# ESP32-C3.net
KiCad netlist of a schematic drawn in Altium Designer
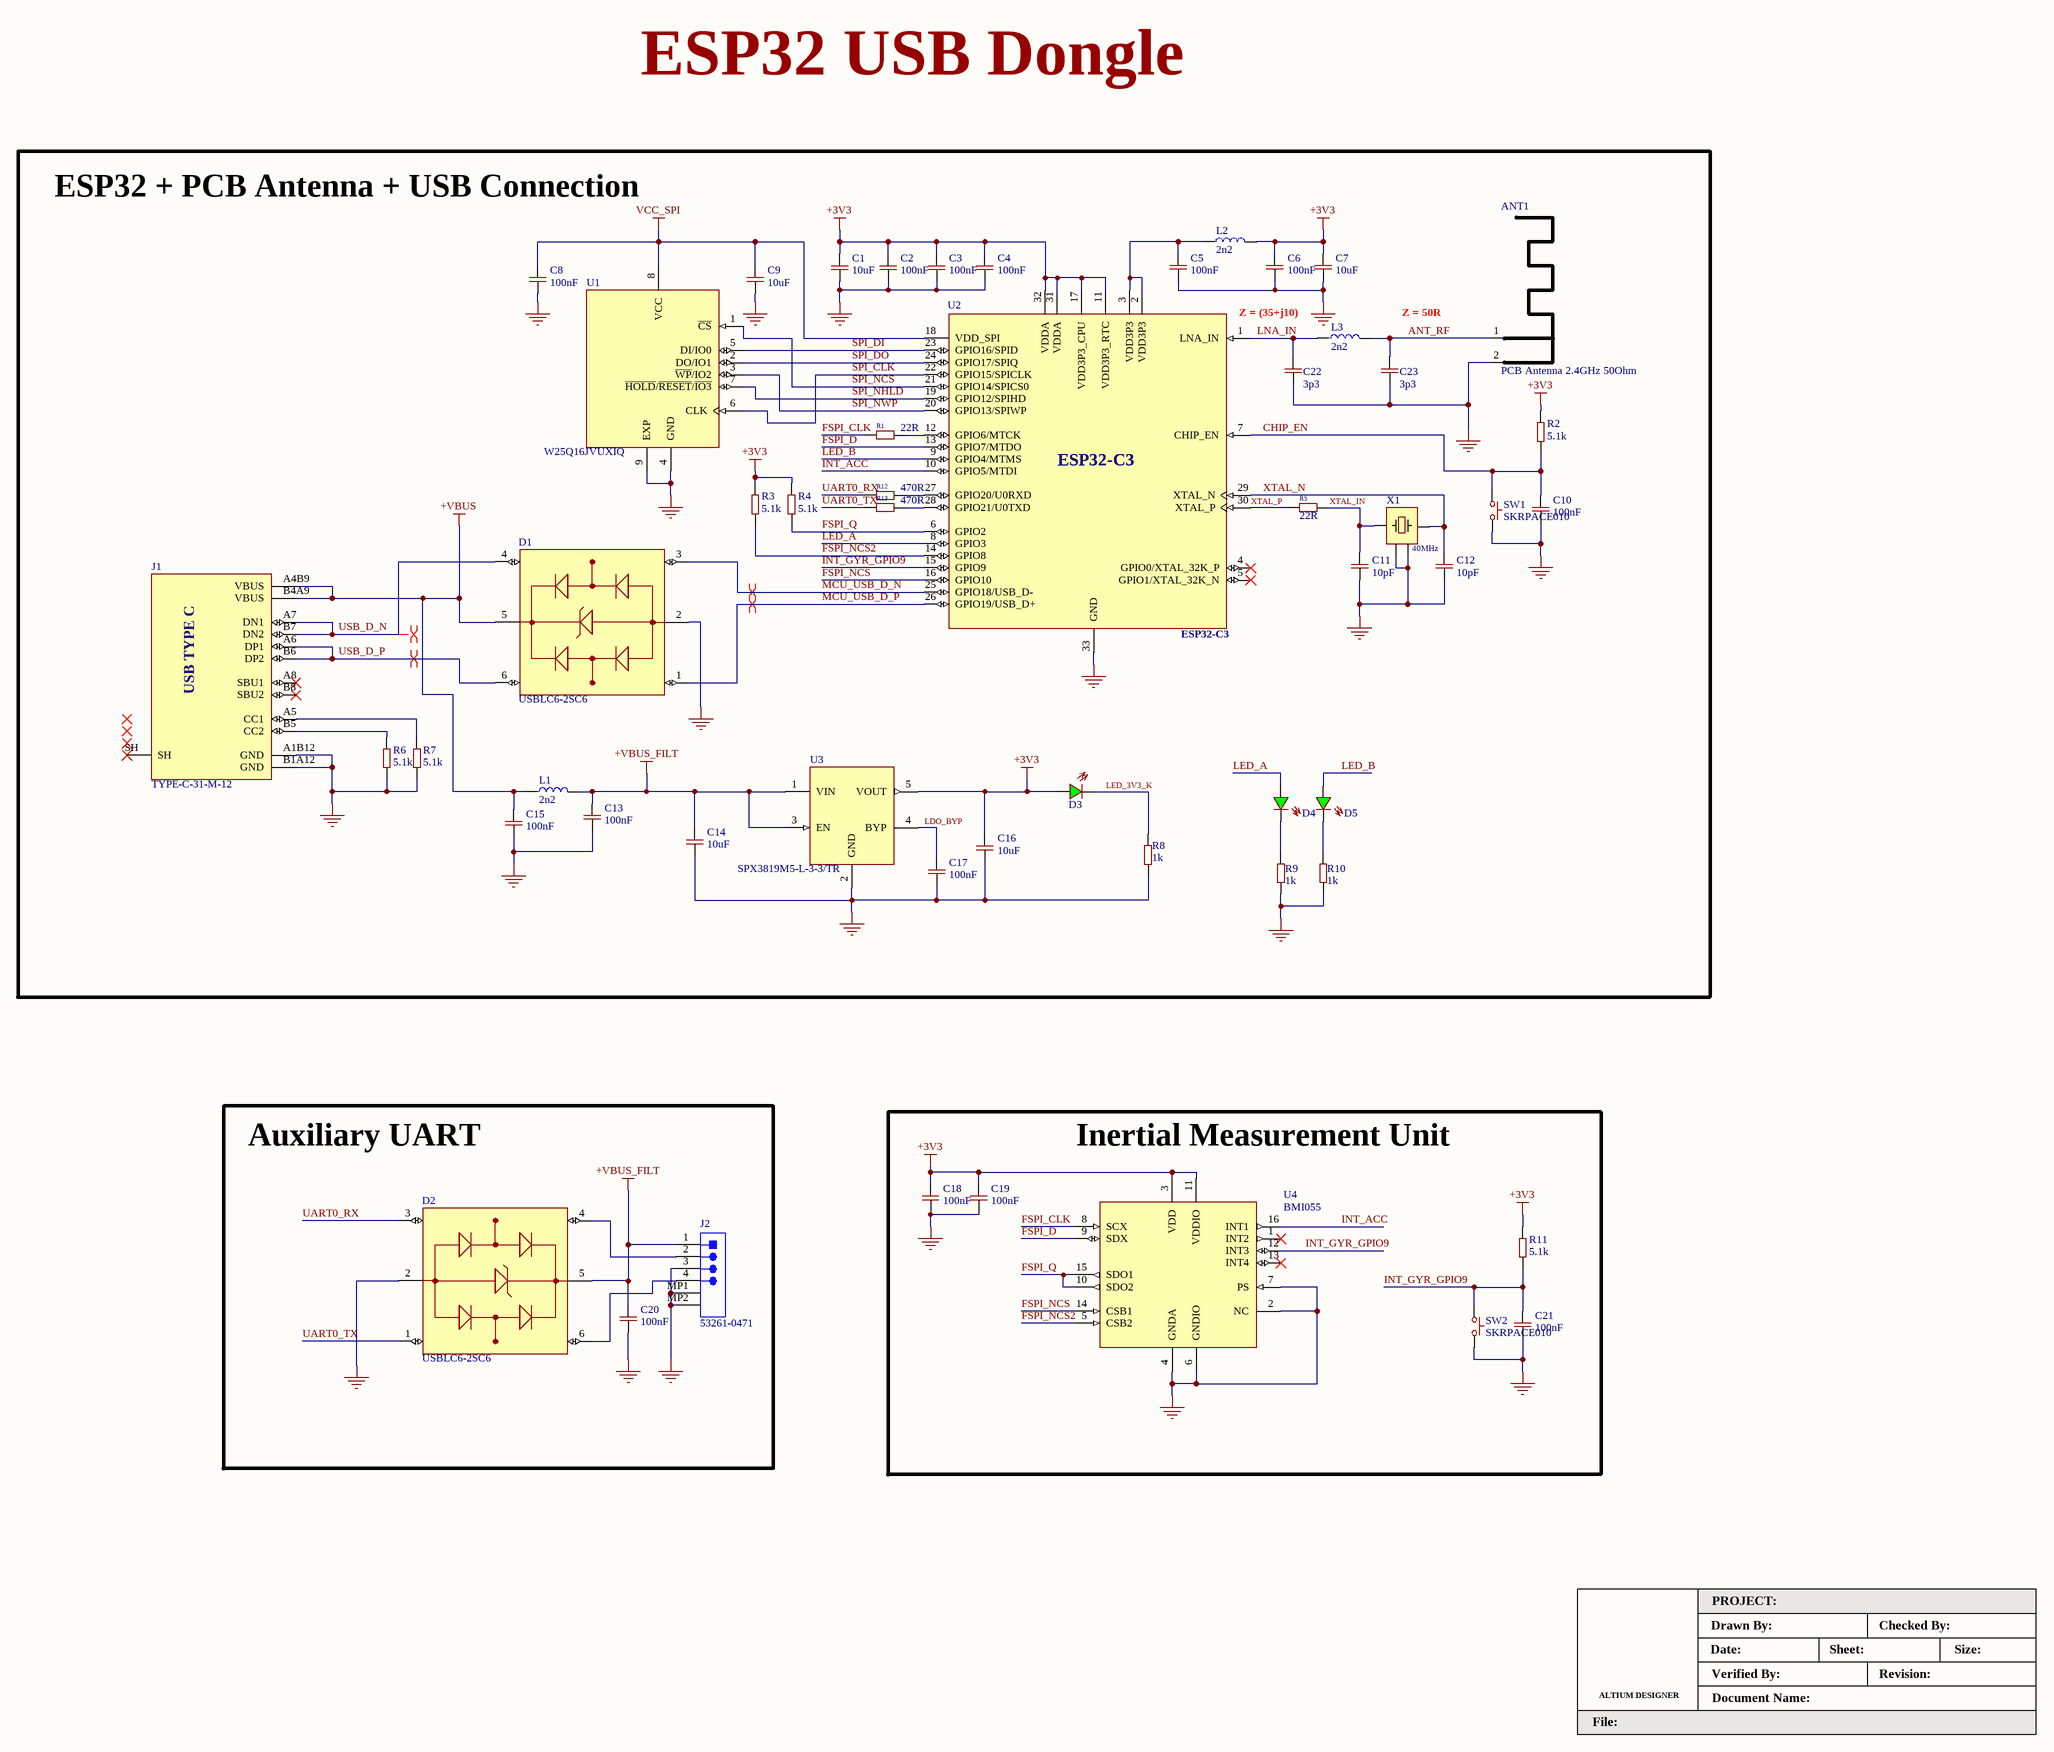
[diagram p0: ESP32-C3.SchDoc]

(export (version "E")
  (design (tool "Eeschema 10.0.6"))
  (components
    (comp (ref "ANT1")
      (value "PCB Antenna 2.4GHz 50Ohm")
      (footprint "ANT_IFA_USB_2_4GHz_50R")
      (description "Inverted F 2.4GHz ISM PCB Antenna 50Ohm")
      (libsource (lib "Schlib_ESP32C3") (part "ANT_IFA_USB_2_4GHz_50R"))
    )
    (comp (ref "C1")
      (value "10uF")
      (footprint "CAP_0603")
      (fields
        (field (name "MANUFACTURER") "Samsung Electro-Mechanics")
        (field (name "MANUFACTURER PART NUMBER") "CL10A106KP8NNNC")
        (field (name "TOLERANCE") "10%")
      )
      (libsource (lib "Schlib_ESP32C3") (part "CAP_0603"))
    )
    (comp (ref "C2")
      (value "100nF")
      (footprint "CAP_0402")
      (fields
        (field (name "MANUFACTURER") "Samsung Electro-Mechanics")
        (field (name "MANUFACTURER PART NUMBER") "CL05B104KO5NNNC")
        (field (name "TOLERANCE") "10%")
      )
      (libsource (lib "Schlib_ESP32C3") (part "CAP_0402"))
    )
    (comp (ref "C3")
      (value "100nF")
      (footprint "CAP_0402")
      (fields
        (field (name "MANUFACTURER") "Samsung Electro-Mechanics")
        (field (name "MANUFACTURER PART NUMBER") "CL05B104KO5NNNC")
        (field (name "TOLERANCE") "10%")
      )
      (libsource (lib "Schlib_ESP32C3") (part "CAP_0402"))
    )
    (comp (ref "C4")
      (value "100nF")
      (footprint "CAP_0402")
      (fields
        (field (name "MANUFACTURER") "Samsung Electro-Mechanics")
        (field (name "MANUFACTURER PART NUMBER") "CL05B104KO5NNNC")
        (field (name "TOLERANCE") "10%")
      )
      (libsource (lib "Schlib_ESP32C3") (part "CAP_0402"))
    )
    (comp (ref "C5")
      (value "100nF")
      (footprint "CAP_0402")
      (fields
        (field (name "MANUFACTURER") "Samsung Electro-Mechanics")
        (field (name "MANUFACTURER PART NUMBER") "CL05B104KO5NNNC")
        (field (name "TOLERANCE") "10%")
      )
      (libsource (lib "Schlib_ESP32C3") (part "CAP_0402"))
    )
    (comp (ref "C6")
      (value "100nF")
      (footprint "CAP_0402")
      (fields
        (field (name "MANUFACTURER") "Samsung Electro-Mechanics")
        (field (name "MANUFACTURER PART NUMBER") "CL05B104KO5NNNC")
        (field (name "TOLERANCE") "10%")
      )
      (libsource (lib "Schlib_ESP32C3") (part "CAP_0402"))
    )
    (comp (ref "C7")
      (value "10uF")
      (footprint "CAP_0603")
      (fields
        (field (name "MANUFACTURER") "Samsung Electro-Mechanics")
        (field (name "MANUFACTURER PART NUMBER") "CL10A106KP8NNNC")
        (field (name "TOLERANCE") "10%")
      )
      (libsource (lib "Schlib_ESP32C3") (part "CAP_0603"))
    )
    (comp (ref "C8")
      (value "100nF")
      (footprint "CAP_0402")
      (fields
        (field (name "MANUFACTURER") "Samsung Electro-Mechanics")
        (field (name "MANUFACTURER PART NUMBER") "CL05B104KO5NNNC")
        (field (name "TOLERANCE") "10%")
      )
      (libsource (lib "Schlib_ESP32C3") (part "CAP_0402"))
    )
    (comp (ref "C9")
      (value "10uF")
      (footprint "CAP_0603")
      (fields
        (field (name "MANUFACTURER") "Samsung Electro-Mechanics")
        (field (name "MANUFACTURER PART NUMBER") "CL10A106KP8NNNC")
        (field (name "TOLERANCE") "10%")
      )
      (libsource (lib "Schlib_ESP32C3") (part "CAP_0603"))
    )
    (comp (ref "C10")
      (value "100nF")
      (footprint "CAP_0402")
      (fields
        (field (name "MANUFACTURER") "Samsung Electro-Mechanics")
        (field (name "MANUFACTURER PART NUMBER") "CL05B104KO5NNNC")
        (field (name "TOLERANCE") "10%")
      )
      (libsource (lib "Schlib_ESP32C3") (part "CAP_0402"))
    )
    (comp (ref "C11")
      (value "10pF")
      (footprint "CAP_0402")
      (fields
        (field (name "MANUFACTURER") "Samsung Electro-Mechanics")
        (field (name "MANUFACTURER PART NUMBER") "CL05C100JB5NNNC")
        (field (name "TOLERANCE") "5%")
      )
      (libsource (lib "Schlib_ESP32C3") (part "CAP_0402"))
    )
    (comp (ref "C12")
      (value "10pF")
      (footprint "CAP_0402")
      (fields
        (field (name "MANUFACTURER") "Samsung Electro-Mechanics")
        (field (name "MANUFACTURER PART NUMBER") "CL05C100JB5NNNC")
        (field (name "TOLERANCE") "5%")
      )
      (libsource (lib "Schlib_ESP32C3") (part "CAP_0402"))
    )
    (comp (ref "C13")
      (value "100nF")
      (footprint "CAP_0402")
      (fields
        (field (name "MANUFACTURER") "Samsung Electro-Mechanics")
        (field (name "MANUFACTURER PART NUMBER") "CL05B104KO5NNNC")
        (field (name "TOLERANCE") "10%")
      )
      (libsource (lib "Schlib_ESP32C3") (part "CAP_0402"))
    )
    (comp (ref "C14")
      (value "10uF")
      (footprint "CAP_0603")
      (fields
        (field (name "MANUFACTURER") "Samsung Electro-Mechanics")
        (field (name "MANUFACTURER PART NUMBER") "CL10A106KP8NNNC")
        (field (name "TOLERANCE") "10%")
      )
      (libsource (lib "Schlib_ESP32C3") (part "CAP_0603"))
    )
    (comp (ref "C15")
      (value "100nF")
      (footprint "CAP_0402")
      (fields
        (field (name "MANUFACTURER") "Samsung Electro-Mechanics")
        (field (name "MANUFACTURER PART NUMBER") "CL05B104KO5NNNC")
        (field (name "TOLERANCE") "10%")
      )
      (libsource (lib "Schlib_ESP32C3") (part "CAP_0402"))
    )
    (comp (ref "C16")
      (value "10uF")
      (footprint "CAP_0603")
      (fields
        (field (name "MANUFACTURER") "Samsung Electro-Mechanics")
        (field (name "MANUFACTURER PART NUMBER") "CL10A106KP8NNNC")
        (field (name "TOLERANCE") "10%")
      )
      (libsource (lib "Schlib_ESP32C3") (part "CAP_0603"))
    )
    (comp (ref "C17")
      (value "100nF")
      (footprint "CAP_0402")
      (fields
        (field (name "MANUFACTURER") "Samsung Electro-Mechanics")
        (field (name "MANUFACTURER PART NUMBER") "CL05B104KO5NNNC")
        (field (name "TOLERANCE") "10%")
      )
      (libsource (lib "Schlib_ESP32C3") (part "CAP_0402"))
    )
    (comp (ref "C18")
      (value "100nF")
      (footprint "CAP_0402")
      (fields
        (field (name "MANUFACTURER") "Samsung Electro-Mechanics")
        (field (name "MANUFACTURER PART NUMBER") "CL05B104KO5NNNC")
        (field (name "TOLERANCE") "10%")
      )
      (libsource (lib "Schlib_ESP32C3") (part "CAP_0402"))
    )
    (comp (ref "C19")
      (value "100nF")
      (footprint "CAP_0402")
      (fields
        (field (name "MANUFACTURER") "Samsung Electro-Mechanics")
        (field (name "MANUFACTURER PART NUMBER") "CL05B104KO5NNNC")
        (field (name "TOLERANCE") "10%")
      )
      (libsource (lib "Schlib_ESP32C3") (part "CAP_0402"))
    )
    (comp (ref "C20")
      (value "100nF")
      (footprint "CAP_0402")
      (fields
        (field (name "MANUFACTURER") "Samsung Electro-Mechanics")
        (field (name "MANUFACTURER PART NUMBER") "CL05B104KO5NNNC")
        (field (name "TOLERANCE") "10%")
      )
      (libsource (lib "Schlib_ESP32C3") (part "CAP_0402"))
    )
    (comp (ref "C21")
      (value "100nF")
      (footprint "CAP_0402")
      (fields
        (field (name "MANUFACTURER") "Samsung Electro-Mechanics")
        (field (name "MANUFACTURER PART NUMBER") "CL05B104KO5NNNC")
        (field (name "TOLERANCE") "10%")
      )
      (libsource (lib "Schlib_ESP32C3") (part "CAP_0402"))
    )
    (comp (ref "C22")
      (value "3p3")
      (footprint "CAP_0402")
      (description "3.3pF 50V Ceramic Capacitor C0G 0402")
      (fields (field (name "MANUFACTURER") "FH") (field (name "MANUFACTURER PART NUMBER") "0402CG3R3C500NT"))
      (libsource (lib "Schlib_ESP32C3") (part "CAP_0402"))
    )
    (comp (ref "C23")
      (value "3p3")
      (footprint "CAP_0402")
      (description "3.3pF 50V Ceramic Capacitor C0G 0402")
      (fields (field (name "MANUFACTURER") "FH") (field (name "MANUFACTURER PART NUMBER") "0402CG3R3C500NT"))
      (libsource (lib "Schlib_ESP32C3") (part "CAP_0402"))
    )
    (comp (ref "D1")
      (value "USBLC6-2SC6")
      (footprint "USBLC6-2SC6")
      (description "STMicroelectronics USBLC6-2SC6 TVS diode surge protection on full tape reel")
      (fields (field (name "MANUFACTURER") "STMicroelectronics"))
      (libsource (lib "Schlib_ESP32C3") (part "USBLC6-2SC6"))
    )
    (comp (ref "D2")
      (value "USBLC6-2SC6")
      (footprint "USBLC6-2SC6")
      (description "STMicroelectronics USBLC6-2SC6 TVS diode surge protection on full tape reel")
      (fields (field (name "MANUFACTURER") "STMicroelectronics"))
      (libsource (lib "Schlib_ESP32C3") (part "USBLC6-2SC6"))
    )
    (comp (ref "D3")
      (value "16-213/GHC-YR1S1/3T")
      (footprint "LED_0402_GREEN_SMD")
      (description "Emerald Green 518nm LED Indication - Discrete 0402")
      (fields (field (name "MANUFACTURER") "EVERLIGHT"))
      (libsource (lib "Schlib_ESP32C3") (part "LED_0402_GREEN_SMD"))
    )
    (comp (ref "D4")
      (value "16-213/GHC-YR1S1/3T")
      (footprint "LED_0402_GREEN_SMD")
      (description "Emerald Green 518nm LED Indication - Discrete 0402")
      (fields (field (name "MANUFACTURER") "EVERLIGHT"))
      (libsource (lib "Schlib_ESP32C3") (part "LED_0402_GREEN_SMD"))
    )
    (comp (ref "D5")
      (value "16-213/GHC-YR1S1/3T")
      (footprint "LED_0402_GREEN_SMD")
      (description "Emerald Green 518nm LED Indication - Discrete 0402")
      (fields (field (name "MANUFACTURER") "EVERLIGHT"))
      (libsource (lib "Schlib_ESP32C3") (part "LED_0402_GREEN_SMD"))
    )
    (comp (ref "J1")
      (value "TYPE-C-31-M-12")
      (footprint "TYPE-C-31-M-12")
      (description "USB-C (USB TYPE-C) Receptacle Connector 16 Position Surface Mount")
      (fields (field (name "MANUFACTURER") "Korean Hroparts Elec"))
      (libsource (lib "Schlib_ESP32C3") (part "TYPE-C-31-M-12"))
    )
    (comp (ref "J2")
      (value "53261-0471")
      (footprint "MOLEX-53261-0471_V")
      (description "Male Header, Pitch 1.25 mm, 1 x 4 Position, Height 3.4 mm, -40 to 85 degC, RoHS, Tape and Reel")
      (fields (field (name "MANUFACTURER") "MOLEX") (field (name "MANUFACTURER PART NUMBER") "532610471"))
      (libsource (lib "Schlib_ESP32C3") (part "CMP-2000-05238-1"))
    )
    (comp (ref "L1")
      (value "2n2")
      (footprint "IND_SMD_0402")
      (description "IND_SMD_0402")
      (fields
        (field (name "MANUFACTURER") "muRata")
        (field (name "MANUFACTURER PART NUMBER") "LQW15AN2N2G80D")
      )
      (libsource (lib "Schlib_ESP32C3") (part "IND_SMD_0402"))
    )
    (comp (ref "L2")
      (value "2n2")
      (footprint "IND_SMD_0402")
      (description "IND_SMD_0402")
      (fields
        (field (name "MANUFACTURER") "muRata")
        (field (name "MANUFACTURER PART NUMBER") "LQW15AN2N2G80D")
      )
      (libsource (lib "Schlib_ESP32C3") (part "IND_SMD_0402"))
    )
    (comp (ref "L3")
      (value "2n2")
      (footprint "IND_SMD_0402")
      (description "IND_SMD_0402")
      (fields
        (field (name "MANUFACTURER") "muRata")
        (field (name "MANUFACTURER PART NUMBER") "LQW15AN2N2G80D")
      )
      (libsource (lib "Schlib_ESP32C3") (part "IND_SMD_0402"))
    )
    (comp (ref "R1")
      (value "22R")
      (footprint "RES_0402")
      (description "22Ω 62.5mW 50V ±100ppm/℃ Thick Film Resistor ±1% 0402 Chip Resistor - Surface Mount RoHS")
      (fields
        (field (name "MANUFACTURER") "UNI-ROYAL")
        (field (name "MANUFACTURER PART NUMBER") "0402WGF220JTCE")
      )
      (libsource (lib "") (part "RES_0402_1"))
    )
    (comp (ref "R2")
      (value "5.1k")
      (footprint "RES_0402")
      (description "5.1kΩ 62.5mW 50V ±100ppm/℃ Thick Film Resistor ±1% 0402 Chip Resistor - Surface Mount RoHS")
      (fields
        (field (name "MANUFACTURER") "UNI-ROYAL")
        (field (name "MANUFACTURER PART NUMBER") "0402WGF5101TCE")
      )
      (libsource (lib "Schlib_ESP32C3") (part "RES_0402"))
    )
    (comp (ref "R3")
      (value "5.1k")
      (footprint "RES_0402")
      (description "5.1kΩ 62.5mW 50V ±100ppm/℃ Thick Film Resistor ±1% 0402 Chip Resistor - Surface Mount RoHS")
      (fields
        (field (name "MANUFACTURER") "UNI-ROYAL")
        (field (name "MANUFACTURER PART NUMBER") "0402WGF5101TCE")
      )
      (libsource (lib "Schlib_ESP32C3") (part "RES_0402"))
    )
    (comp (ref "R4")
      (value "5.1k")
      (footprint "RES_0402")
      (description "5.1kΩ 62.5mW 50V ±100ppm/℃ Thick Film Resistor ±1% 0402 Chip Resistor - Surface Mount RoHS")
      (fields
        (field (name "MANUFACTURER") "UNI-ROYAL")
        (field (name "MANUFACTURER PART NUMBER") "0402WGF5101TCE")
      )
      (libsource (lib "Schlib_ESP32C3") (part "RES_0402"))
    )
    (comp (ref "R5")
      (value "22R")
      (footprint "RES_0402")
      (description "22Ω 62.5mW 50V ±100ppm/℃ Thick Film Resistor ±1% 0402 Chip Resistor - Surface Mount RoHS")
      (fields
        (field (name "MANUFACTURER") "UNI-ROYAL")
        (field (name "MANUFACTURER PART NUMBER") "0402WGF220JTCE")
      )
      (libsource (lib "") (part "RES_0402_1"))
    )
    (comp (ref "R6")
      (value "5.1k")
      (footprint "RES_0402")
      (description "5.1 kOhms ±5% 0.063W, 1/16W Chip Resistor 0402 (1005 Metric) Moisture Resistant Thick Film")
      (fields
        (field (name "MANUFACTURER") "YAGEO")
        (field (name "MANUFACTURER PART NUMBER") "RC0402JR-075K1L")
      )
      (libsource (lib "Schlib_ESP32C3") (part "RES_0402"))
    )
    (comp (ref "R7")
      (value "5.1k")
      (footprint "RES_0402")
      (description "5.1 kOhms ±5% 0.063W, 1/16W Chip Resistor 0402 (1005 Metric) Moisture Resistant Thick Film")
      (fields
        (field (name "MANUFACTURER") "YAGEO")
        (field (name "MANUFACTURER PART NUMBER") "RC0402JR-075K1L")
      )
      (libsource (lib "Schlib_ESP32C3") (part "RES_0402"))
    )
    (comp (ref "R8")
      (value "1k")
      (footprint "RES_0402")
      (description "1kΩ ±1% 62.5mW 0402 Thick Film Resistor")
      (fields
        (field (name "MANUFACTURER") "UNI-ROYAL")
        (field (name "MANUFACTURER PART NUMBER") "0402WGF1001TCE")
      )
      (libsource (lib "Schlib_ESP32C3") (part "RES_0402"))
    )
    (comp (ref "R9")
      (value "1k")
      (footprint "RES_0402")
      (description "1kΩ ±1% 62.5mW 0402 Thick Film Resistor")
      (fields
        (field (name "MANUFACTURER") "UNI-ROYAL")
        (field (name "MANUFACTURER PART NUMBER") "0402WGF1001TCE")
      )
      (libsource (lib "Schlib_ESP32C3") (part "RES_0402"))
    )
    (comp (ref "R10")
      (value "1k")
      (footprint "RES_0402")
      (description "1kΩ ±1% 62.5mW 0402 Thick Film Resistor")
      (fields
        (field (name "MANUFACTURER") "UNI-ROYAL")
        (field (name "MANUFACTURER PART NUMBER") "0402WGF1001TCE")
      )
      (libsource (lib "Schlib_ESP32C3") (part "RES_0402"))
    )
    (comp (ref "R11")
      (value "5.1k")
      (footprint "RES_0402")
      (description "5.1kΩ 62.5mW 50V ±100ppm/℃ Thick Film Resistor ±1% 0402 Chip Resistor - Surface Mount RoHS")
      (fields
        (field (name "MANUFACTURER") "UNI-ROYAL")
        (field (name "MANUFACTURER PART NUMBER") "0402WGF5101TCE")
      )
      (libsource (lib "Schlib_ESP32C3") (part "RES_0402"))
    )
    (comp (ref "R12")
      (value "470R")
      (footprint "RES_0402")
      (description "470Ω ±1% 62.5mW 0402 Thick Film Resistor")
      (fields
        (field (name "MANUFACTURER") "UNI-ROYAL")
        (field (name "MANUFACTURER PART NUMBER") "0402WGF4700TCE")
      )
      (libsource (lib "") (part "RES_0402_1"))
    )
    (comp (ref "R13")
      (value "470R")
      (footprint "RES_0402")
      (description "470Ω ±1% 62.5mW 0402 Thick Film Resistor")
      (fields
        (field (name "MANUFACTURER") "UNI-ROYAL")
        (field (name "MANUFACTURER PART NUMBER") "0402WGF4700TCE")
      )
      (libsource (lib "") (part "RES_0402_1"))
    )
    (comp (ref "SW1")
      (value "SKRPACE010")
      (footprint "Tactile Switch")
      (description "Switch Tactile N.O. SPST Button J-Bend 0.05A 16VDC 2.55N SMD T/R")
      (fields (field (name "MANUFACTURER") "ALPS"))
      (libsource (lib "Schlib_ESP32C3") (part "Tactile Switch"))
    )
    (comp (ref "SW2")
      (value "SKRPACE010")
      (footprint "Tactile Switch")
      (description "Switch Tactile N.O. SPST Button J-Bend 0.05A 16VDC 2.55N SMD T/R")
      (fields (field (name "MANUFACTURER") "ALPS"))
      (libsource (lib "Schlib_ESP32C3") (part "Tactile Switch"))
    )
    (comp (ref "U1")
      (value "W25Q16JVUXIQ")
      (footprint "W25Q16JVUXIQ")
      (description "NOR Flash Serial (SPI, Dual SPI, Quad SPI) 3V/3.3V 16M-bit 2M x 8 6ns 8-Pin USON EP T/R")
      (fields
        (field (name "MANUFACTURER") "Winbond")
        (field (name "MANUFACTURER PART NUMBER") "W25Q16JVUXIQ TR")
      )
      (libsource (lib "Schlib_ESP32C3") (part "W25Q16JVUXIQ"))
    )
    (comp (ref "U2")
      (value "ESP32-C3")
      (footprint "ESP32-C3")
      (description "400KB 22 3V~3.6V RISC-V 160MHz QFN-32-EP(5x5) Microcontroller Units (MCUs/MPUs/SOCs) ROHS")
      (fields (field (name "MANUFACTURER") "Espressif Systems"))
      (libsource (lib "Schlib_ESP32C3") (part "ESP32-C3"))
    )
    (comp (ref "U3")
      (value "SPX3819M5-L-3-3/TR")
      (footprint "SPX3819M5-L-3-3/TR")
      (description "SPX3819 Series 3.3 V 500 mA Fixed Output SMT LDO Regulator - SOT-23-5")
      (fields (field (name "MANUFACTURER") "MaxLinear"))
      (libsource (lib "Schlib_ESP32C3") (part "SPX3819M5-L-3-3/TR"))
    )
    (comp (ref "U4")
      (value "BMI055")
      (footprint "BMI055")
      (description "LGA-16(3x4.5) Accelerometers RoHS")
      (fields (field (name "MANUFACTURER") "Bosch"))
      (libsource (lib "Schlib_ESP32C3") (part "BMI055"))
    )
    (comp (ref "X1")
      (value "40MHz")
      (footprint "XTAL_40MHz_2520")
      (description "Crystal 40MHz ±10ppm (Tol) ±20ppm (Stability) 9pF FUND 40Ohm 4-Pin Ultra Mini-CSMD T/R")
      (fields
        (field (name "MANUFACTURER") "Epson")
        (field (name "MANUFACTURER PART NUMBER") "FA-20H 40.0000MF20X-AC3")
      )
      (libsource (lib "Schlib_ESP32C3") (part "XTAL_40MHz_2520"))
    )
  )
  (nets
    (net (code "1") (name "+3V3") (class "Default")
      (node (ref "C1") (pin "2") (pinfunction "2_2") (pintype "passive"))
      (node (ref "C16") (pin "2") (pinfunction "2_2") (pintype "passive"))
      (node (ref "C18") (pin "2") (pinfunction "2_2") (pintype "passive"))
      (node (ref "C19") (pin "2") (pinfunction "2_2") (pintype "passive"))
      (node (ref "C2") (pin "2") (pinfunction "2_2") (pintype "passive"))
      (node (ref "C3") (pin "2") (pinfunction "2_2") (pintype "passive"))
      (node (ref "C4") (pin "2") (pinfunction "2_2") (pintype "passive"))
      (node (ref "C6") (pin "2") (pinfunction "2_2") (pintype "passive"))
      (node (ref "C7") (pin "2") (pinfunction "2_2") (pintype "passive"))
      (node (ref "D3") (pin "A") (pinfunction "A_A") (pintype "passive"))
      (node (ref "L2") (pin "2") (pinfunction "2_2") (pintype "passive"))
      (node (ref "R11") (pin "2") (pinfunction "2_2") (pintype "passive"))
      (node (ref "R2") (pin "2") (pinfunction "2_2") (pintype "passive"))
      (node (ref "R3") (pin "2") (pinfunction "2_2") (pintype "passive"))
      (node (ref "R4") (pin "2") (pinfunction "2_2") (pintype "passive"))
      (node (ref "U2") (pin "11") (pinfunction "VDD3P3_RTC_11") (pintype "power_in"))
      (node (ref "U2") (pin "17") (pinfunction "VDD3P3_CPU_17") (pintype "power_in"))
      (node (ref "U2") (pin "31") (pinfunction "VDDA_31") (pintype "power_in"))
      (node (ref "U2") (pin "32") (pinfunction "VDDA_32") (pintype "power_in"))
      (node (ref "U3") (pin "5") (pinfunction "VOUT_5") (pintype "output"))
      (node (ref "U4") (pin "11") (pinfunction "VDDIO_11") (pintype "power_in"))
      (node (ref "U4") (pin "3") (pinfunction "VDD_3") (pintype "power_in"))
    )
    (net (code "2") (name "+VBUS") (class "Default")
      (node (ref "C15") (pin "2") (pinfunction "2_2") (pintype "passive"))
      (node (ref "D1") (pin "5") (pinfunction "VBUS_5") (pintype "power_in"))
      (node (ref "J1") (pin "A4B9") (pinfunction "VBUS_A4B9") (pintype "power_in"))
      (node (ref "J1") (pin "B4A9") (pinfunction "VBUS_B4A9") (pintype "power_in"))
      (node (ref "L1") (pin "1") (pinfunction "1_1") (pintype "passive"))
    )
    (net (code "3") (name "+VBUS_FILT") (class "Default")
      (node (ref "C13") (pin "2") (pinfunction "2_2") (pintype "passive"))
      (node (ref "C14") (pin "2") (pinfunction "2_2") (pintype "passive"))
      (node (ref "C20") (pin "2") (pinfunction "2_2") (pintype "passive"))
      (node (ref "D2") (pin "5") (pinfunction "VBUS_5") (pintype "power_in"))
      (node (ref "J2") (pin "1") (pinfunction "1_1") (pintype "passive"))
      (node (ref "L1") (pin "2") (pinfunction "2_2") (pintype "passive"))
      (node (ref "U3") (pin "1") (pinfunction "VIN_1") (pintype "power_in"))
      (node (ref "U3") (pin "3") (pinfunction "EN_3") (pintype "input"))
    )
    (net (code "4") (name "/ANT_RF") (class "Default")
      (node (ref "ANT1") (pin "1") (pinfunction "RF_1") (pintype "passive"))
      (node (ref "C23") (pin "2") (pinfunction "2_2") (pintype "passive"))
      (node (ref "L3") (pin "2") (pinfunction "2_2") (pintype "passive"))
    )
    (net (code "5") (name "/CHIP_EN") (class "Default")
      (node (ref "C10") (pin "2") (pinfunction "2_2") (pintype "passive"))
      (node (ref "R2") (pin "1") (pinfunction "1_1") (pintype "passive"))
      (node (ref "SW1") (pin "12") (pinfunction "12_12") (pintype "passive"))
      (node (ref "U2") (pin "7") (pinfunction "CHIP_EN_7") (pintype "input"))
    )
    (net (code "6") (name "/FSPI_CLK") (class "Default")
      (node (ref "R1") (pin "1") (pinfunction "1_1") (pintype "passive"))
      (node (ref "U4") (pin "8") (pinfunction "SCX_8") (pintype "input"))
    )
    (net (code "7") (name "/FSPI_D") (class "Default")
      (node (ref "U2") (pin "13") (pinfunction "GPIO7/MTDO_13") (pintype "bidirectional"))
      (node (ref "U4") (pin "9") (pinfunction "SDX_9") (pintype "bidirectional"))
    )
    (net (code "8") (name "/FSPI_NCS") (class "Default")
      (node (ref "U2") (pin "16") (pinfunction "GPIO10_16") (pintype "bidirectional"))
      (node (ref "U4") (pin "14") (pinfunction "CSB1_14") (pintype "input"))
    )
    (net (code "9") (name "/FSPI_NCS2") (class "Default")
      (node (ref "R3") (pin "1") (pinfunction "1_1") (pintype "passive"))
      (node (ref "U2") (pin "14") (pinfunction "GPIO8_14") (pintype "bidirectional"))
      (node (ref "U4") (pin "5") (pinfunction "CSB2_5") (pintype "input"))
    )
    (net (code "10") (name "/FSPI_Q") (class "Default")
      (node (ref "R4") (pin "1") (pinfunction "1_1") (pintype "passive"))
      (node (ref "U2") (pin "6") (pinfunction "GPIO2_6") (pintype "bidirectional"))
      (node (ref "U4") (pin "10") (pinfunction "SDO2_10") (pintype "output"))
      (node (ref "U4") (pin "15") (pinfunction "SDO1_15") (pintype "output"))
    )
    (net (code "11") (name "/INT_ACC") (class "Default")
      (node (ref "U2") (pin "10") (pinfunction "GPIO5/MTDI_10") (pintype "bidirectional"))
      (node (ref "U4") (pin "16") (pinfunction "INT1_16") (pintype "output"))
    )
    (net (code "12") (name "/INT_GYR_GPIO9") (class "Default")
      (node (ref "C21") (pin "2") (pinfunction "2_2") (pintype "passive"))
      (node (ref "R11") (pin "1") (pinfunction "1_1") (pintype "passive"))
      (node (ref "SW2") (pin "12") (pinfunction "12_12") (pintype "passive"))
      (node (ref "U2") (pin "15") (pinfunction "GPIO9_15") (pintype "bidirectional"))
      (node (ref "U4") (pin "12") (pinfunction "INT3_12") (pintype "bidirectional"))
    )
    (net (code "13") (name "/LDO_BYP") (class "Default")
      (node (ref "C17") (pin "2") (pinfunction "2_2") (pintype "passive"))
      (node (ref "U3") (pin "4") (pinfunction "BYP_4") (pintype "passive"))
    )
    (net (code "14") (name "/LED_3V3_K") (class "Default")
      (node (ref "D3") (pin "K") (pinfunction "K_K") (pintype "passive"))
      (node (ref "R8") (pin "2") (pinfunction "2_2") (pintype "passive"))
    )
    (net (code "15") (name "/LED_A") (class "Default")
      (node (ref "D4") (pin "A") (pinfunction "A_A") (pintype "passive"))
      (node (ref "U2") (pin "8") (pinfunction "GPIO3_8") (pintype "bidirectional"))
    )
    (net (code "16") (name "/LED_B") (class "Default")
      (node (ref "D5") (pin "A") (pinfunction "A_A") (pintype "passive"))
      (node (ref "U2") (pin "9") (pinfunction "GPIO4/MTMS_9") (pintype "bidirectional"))
    )
    (net (code "17") (name "/LNA_IN") (class "Default")
      (node (ref "C22") (pin "2") (pinfunction "2_2") (pintype "passive"))
      (node (ref "L3") (pin "1") (pinfunction "1_1") (pintype "passive"))
      (node (ref "U2") (pin "1") (pinfunction "LNA_IN_1") (pintype "input"))
    )
    (net (code "18") (name "/MCU_USB_D_N") (class "Default")
      (node (ref "D1") (pin "3") (pinfunction "I/O2_IN_3") (pintype "bidirectional"))
      (node (ref "U2") (pin "25") (pinfunction "GPIO18/USB_D-_25") (pintype "bidirectional"))
    )
    (net (code "19") (name "/MCU_USB_D_P") (class "Default")
      (node (ref "D1") (pin "1") (pinfunction "I/O1_IN_1") (pintype "bidirectional"))
      (node (ref "U2") (pin "26") (pinfunction "GPIO19/USB_D+_26") (pintype "bidirectional"))
    )
    (net (code "20") (name "/SPI_CLK") (class "Default")
      (node (ref "U1") (pin "6") (pinfunction "CLK_6") (pintype "input"))
      (node (ref "U2") (pin "22") (pinfunction "GPIO15/SPICLK_22") (pintype "bidirectional"))
    )
    (net (code "21") (name "/SPI_DI") (class "Default")
      (node (ref "U1") (pin "5") (pinfunction "DI/IO0_5") (pintype "bidirectional"))
      (node (ref "U2") (pin "23") (pinfunction "GPIO16/SPID_23") (pintype "bidirectional"))
    )
    (net (code "22") (name "/SPI_DO") (class "Default")
      (node (ref "U1") (pin "2") (pinfunction "DO/IO1_2") (pintype "bidirectional"))
      (node (ref "U2") (pin "24") (pinfunction "GPIO17/SPIQ_24") (pintype "bidirectional"))
    )
    (net (code "23") (name "/SPI_NCS") (class "Default")
      (node (ref "U1") (pin "1") (pinfunction "~{CS}_1") (pintype "input"))
      (node (ref "U2") (pin "21") (pinfunction "GPIO14/SPICS0_21") (pintype "bidirectional"))
    )
    (net (code "24") (name "/SPI_NHLD") (class "Default")
      (node (ref "U1") (pin "7") (pinfunction "~{HOLD}/~{RESET}/~{IO3}_7") (pintype "bidirectional"))
      (node (ref "U2") (pin "19") (pinfunction "GPIO12/SPIHD_19") (pintype "bidirectional"))
    )
    (net (code "25") (name "/SPI_NWP") (class "Default")
      (node (ref "U1") (pin "3") (pinfunction "~{WP}/IO2_3") (pintype "bidirectional"))
      (node (ref "U2") (pin "20") (pinfunction "GPIO13/SPIWP_20") (pintype "bidirectional"))
    )
    (net (code "26") (name "/UART0_RX") (class "Default")
      (node (ref "D2") (pin "3") (pinfunction "I/O2_IN_3") (pintype "bidirectional"))
      (node (ref "R12") (pin "1") (pinfunction "1_1") (pintype "passive"))
    )
    (net (code "27") (name "/UART0_TX") (class "Default")
      (node (ref "D2") (pin "1") (pinfunction "I/O1_IN_1") (pintype "bidirectional"))
      (node (ref "R13") (pin "1") (pinfunction "1_1") (pintype "passive"))
    )
    (net (code "28") (name "/USB_D_N") (class "Default")
      (node (ref "D1") (pin "4") (pinfunction "I/O2_OUT_4") (pintype "bidirectional"))
      (node (ref "J1") (pin "A7") (pinfunction "DN1_A7") (pintype "bidirectional"))
      (node (ref "J1") (pin "B7") (pinfunction "DN2_B7") (pintype "bidirectional"))
    )
    (net (code "29") (name "/USB_D_P") (class "Default")
      (node (ref "D1") (pin "6") (pinfunction "I/O1_OUT_6") (pintype "bidirectional"))
      (node (ref "J1") (pin "A6") (pinfunction "DP1_A6") (pintype "bidirectional"))
      (node (ref "J1") (pin "B6") (pinfunction "DP2_B6") (pintype "bidirectional"))
    )
    (net (code "30") (name "/XTAL_IN") (class "Default")
      (node (ref "C11") (pin "2") (pinfunction "2_2") (pintype "passive"))
      (node (ref "R5") (pin "2") (pinfunction "2_2") (pintype "passive"))
      (node (ref "X1") (pin "1") (pinfunction "1_1") (pintype "passive"))
    )
    (net (code "31") (name "/XTAL_N") (class "Default")
      (node (ref "C12") (pin "2") (pinfunction "2_2") (pintype "passive"))
      (node (ref "U2") (pin "29") (pinfunction "XTAL_N_29") (pintype "input"))
      (node (ref "X1") (pin "3") (pinfunction "3_3") (pintype "passive"))
    )
    (net (code "32") (name "/XTAL_P") (class "Default")
      (node (ref "R5") (pin "1") (pinfunction "1_1") (pintype "passive"))
      (node (ref "U2") (pin "30") (pinfunction "XTAL_P_30") (pintype "input"))
    )
    (net (code "33") (name "GND") (class "Default")
      (node (ref "ANT1") (pin "2") (pinfunction "GND_2") (pintype "passive"))
      (node (ref "C1") (pin "1") (pinfunction "1_1") (pintype "passive"))
      (node (ref "C10") (pin "1") (pinfunction "1_1") (pintype "passive"))
      (node (ref "C11") (pin "1") (pinfunction "1_1") (pintype "passive"))
      (node (ref "C12") (pin "1") (pinfunction "1_1") (pintype "passive"))
      (node (ref "C13") (pin "1") (pinfunction "1_1") (pintype "passive"))
      (node (ref "C14") (pin "1") (pinfunction "1_1") (pintype "passive"))
      (node (ref "C15") (pin "1") (pinfunction "1_1") (pintype "passive"))
      (node (ref "C16") (pin "1") (pinfunction "1_1") (pintype "passive"))
      (node (ref "C17") (pin "1") (pinfunction "1_1") (pintype "passive"))
      (node (ref "C18") (pin "1") (pinfunction "1_1") (pintype "passive"))
      (node (ref "C19") (pin "1") (pinfunction "1_1") (pintype "passive"))
      (node (ref "C2") (pin "1") (pinfunction "1_1") (pintype "passive"))
      (node (ref "C20") (pin "1") (pinfunction "1_1") (pintype "passive"))
      (node (ref "C21") (pin "1") (pinfunction "1_1") (pintype "passive"))
      (node (ref "C22") (pin "1") (pinfunction "1_1") (pintype "passive"))
      (node (ref "C23") (pin "1") (pinfunction "1_1") (pintype "passive"))
      (node (ref "C3") (pin "1") (pinfunction "1_1") (pintype "passive"))
      (node (ref "C4") (pin "1") (pinfunction "1_1") (pintype "passive"))
      (node (ref "C5") (pin "1") (pinfunction "1_1") (pintype "passive"))
      (node (ref "C6") (pin "1") (pinfunction "1_1") (pintype "passive"))
      (node (ref "C7") (pin "1") (pinfunction "1_1") (pintype "passive"))
      (node (ref "C8") (pin "1") (pinfunction "1_1") (pintype "passive"))
      (node (ref "C9") (pin "1") (pinfunction "1_1") (pintype "passive"))
      (node (ref "D1") (pin "2") (pinfunction "GND_2") (pintype "power_in"))
      (node (ref "D2") (pin "2") (pinfunction "GND_2") (pintype "power_in"))
      (node (ref "J1") (pin "A1B12") (pinfunction "GND_A1B12") (pintype "power_in"))
      (node (ref "J1") (pin "B1A12") (pinfunction "GND_B1A12") (pintype "power_in"))
      (node (ref "J2") (pin "3") (pinfunction "3_3") (pintype "passive"))
      (node (ref "J2") (pin "MP1") (pinfunction "MP1_MP1") (pintype "passive"))
      (node (ref "J2") (pin "MP2") (pinfunction "MP2_MP2") (pintype "passive"))
      (node (ref "R10") (pin "1") (pinfunction "1_1") (pintype "passive"))
      (node (ref "R6") (pin "1") (pinfunction "1_1") (pintype "passive"))
      (node (ref "R7") (pin "1") (pinfunction "1_1") (pintype "passive"))
      (node (ref "R8") (pin "1") (pinfunction "1_1") (pintype "passive"))
      (node (ref "R9") (pin "1") (pinfunction "1_1") (pintype "passive"))
      (node (ref "SW1") (pin "34") (pinfunction "34_34") (pintype "passive"))
      (node (ref "SW2") (pin "34") (pinfunction "34_34") (pintype "passive"))
      (node (ref "U1") (pin "4") (pinfunction "GND_4") (pintype "power_in"))
      (node (ref "U1") (pin "9") (pinfunction "EXP_9") (pintype "passive"))
      (node (ref "U2") (pin "33") (pinfunction "GND_33") (pintype "power_in"))
      (node (ref "U3") (pin "2") (pinfunction "GND_2") (pintype "passive"))
      (node (ref "U4") (pin "2") (pinfunction "NC_2") (pintype "passive"))
      (node (ref "U4") (pin "4") (pinfunction "GNDA_4") (pintype "passive"))
      (node (ref "U4") (pin "6") (pinfunction "GNDIO_6") (pintype "passive"))
      (node (ref "U4") (pin "7") (pinfunction "PS_7") (pintype "input"))
      (node (ref "X1") (pin "2") (pinfunction "2_2") (pintype "passive"))
      (node (ref "X1") (pin "4") (pinfunction "4_4") (pintype "passive"))
    )
    (net (code "34") (name "Net-(C5-Pad2)") (class "Default")
      (node (ref "C5") (pin "2") (pinfunction "2_2") (pintype "passive"))
      (node (ref "L2") (pin "1") (pinfunction "1_1") (pintype "passive"))
      (node (ref "U2") (pin "2") (pinfunction "VDD3P3_2") (pintype "power_in"))
      (node (ref "U2") (pin "3") (pinfunction "VDD3P3_3") (pintype "power_in"))
    )
    (net (code "35") (name "Net-(D2-I{slash}O1_OUT)") (class "Default")
      (node (ref "D2") (pin "6") (pinfunction "I/O1_OUT_6") (pintype "bidirectional"))
      (node (ref "J2") (pin "4") (pinfunction "4_4") (pintype "passive"))
    )
    (net (code "36") (name "Net-(D2-I{slash}O2_OUT)") (class "Default")
      (node (ref "D2") (pin "4") (pinfunction "I/O2_OUT_4") (pintype "bidirectional"))
      (node (ref "J2") (pin "2") (pinfunction "2_2") (pintype "passive"))
    )
    (net (code "37") (name "Net-(D4-PadK)") (class "Default")
      (node (ref "D4") (pin "K") (pinfunction "K_K") (pintype "passive"))
      (node (ref "R9") (pin "2") (pinfunction "2_2") (pintype "passive"))
    )
    (net (code "38") (name "Net-(D5-PadK)") (class "Default")
      (node (ref "D5") (pin "K") (pinfunction "K_K") (pintype "passive"))
      (node (ref "R10") (pin "2") (pinfunction "2_2") (pintype "passive"))
    )
    (net (code "39") (name "Net-(J1-CC1)") (class "Default")
      (node (ref "J1") (pin "A5") (pinfunction "CC1_A5") (pintype "bidirectional"))
      (node (ref "R7") (pin "2") (pinfunction "2_2") (pintype "passive"))
    )
    (net (code "40") (name "Net-(J1-CC2)") (class "Default")
      (node (ref "J1") (pin "B5") (pinfunction "CC2_B5") (pintype "bidirectional"))
      (node (ref "R6") (pin "2") (pinfunction "2_2") (pintype "passive"))
    )
    (net (code "41") (name "Net-(U2-GPIO6{slash}MTCK)") (class "Default")
      (node (ref "R1") (pin "2") (pinfunction "2_2") (pintype "passive"))
      (node (ref "U2") (pin "12") (pinfunction "GPIO6/MTCK_12") (pintype "bidirectional"))
    )
    (net (code "42") (name "Net-(U2-GPIO20{slash}U0RXD)") (class "Default")
      (node (ref "R12") (pin "2") (pinfunction "2_2") (pintype "passive"))
      (node (ref "U2") (pin "27") (pinfunction "GPIO20/U0RXD_27") (pintype "bidirectional"))
    )
    (net (code "43") (name "Net-(U2-GPIO21{slash}U0TXD)") (class "Default")
      (node (ref "R13") (pin "2") (pinfunction "2_2") (pintype "passive"))
      (node (ref "U2") (pin "28") (pinfunction "GPIO21/U0TXD_28") (pintype "bidirectional"))
    )
    (net (code "44") (name "VCC_SPI") (class "Default")
      (node (ref "C8") (pin "2") (pinfunction "2_2") (pintype "passive"))
      (node (ref "C9") (pin "2") (pinfunction "2_2") (pintype "passive"))
      (node (ref "U1") (pin "8") (pinfunction "VCC_8") (pintype "power_in"))
      (node (ref "U2") (pin "18") (pinfunction "VDD_SPI_18") (pintype "power_in"))
    )
    (net (code "45") (name "unconnected-(J1-PadSH)") (class "Default")
      (node (ref "J1") (pin "SH") (pinfunction "SH_SH") (pintype "passive+no_connect"))
    )
    (net (code "46") (name "unconnected-(J1-SBU1-PadA8)") (class "Default")
      (node (ref "J1") (pin "A8") (pinfunction "SBU1_A8") (pintype "bidirectional+no_connect"))
    )
    (net (code "47") (name "unconnected-(J1-SBU2-PadB8)") (class "Default")
      (node (ref "J1") (pin "B8") (pinfunction "SBU2_B8") (pintype "bidirectional+no_connect"))
    )
    (net (code "48") (name "unconnected-(U2-GPIO0{slash}XTAL_32K_P-Pad4)") (class "Default")
      (node (ref "U2") (pin "4") (pinfunction "GPIO0/XTAL_32K_P_4") (pintype "bidirectional+no_connect"))
    )
    (net (code "49") (name "unconnected-(U2-GPIO1{slash}XTAL_32K_N-Pad5)") (class "Default")
      (node (ref "U2") (pin "5") (pinfunction "GPIO1/XTAL_32K_N_5") (pintype "bidirectional+no_connect"))
    )
    (net (code "50") (name "unconnected-(U4-INT2-Pad1)") (class "Default")
      (node (ref "U4") (pin "1") (pinfunction "INT2_1") (pintype "output+no_connect"))
    )
    (net (code "51") (name "unconnected-(U4-INT4-Pad13)") (class "Default")
      (node (ref "U4") (pin "13") (pinfunction "INT4_13") (pintype "bidirectional+no_connect"))
    )
  )
)
